# PowerSuply.net
KiCad netlist of a schematic drawn in Altium Designer
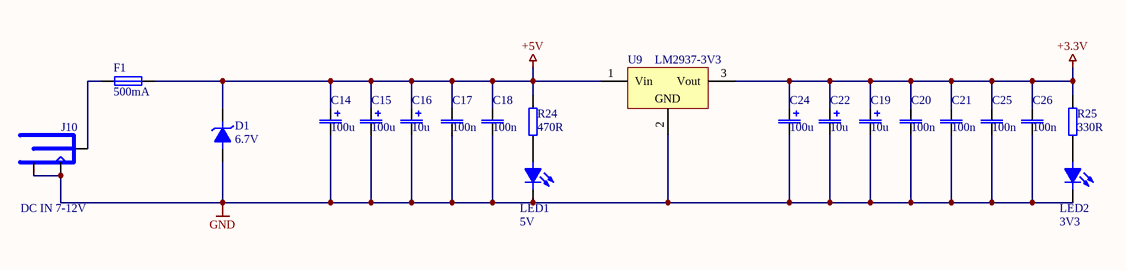
[diagram p0: PowerSuply.SchDoc]

(export (version "E")
  (design (tool "Eeschema 10.0.6"))
  (components
    (comp (ref "C14")
      (value "100u")
      (footprint "D8 ELKO")
      (description "POLARIZED CAPACITOR")
      (libsource (lib "SCH_LIB") (part "CAP_POL"))
    )
    (comp (ref "C15")
      (value "100u")
      (footprint "D8 ELKO")
      (description "POLARIZED CAPACITOR")
      (libsource (lib "SCH_LIB") (part "CAP_POL"))
    )
    (comp (ref "C16")
      (value "10u")
      (footprint "CAP 1210")
      (description "POLARIZED CAPACITOR")
      (libsource (lib "SCH_LIB") (part "CAP_POL"))
    )
    (comp (ref "C17")
      (value "100n")
      (footprint "CAP 0805")
      (description "NON POLARIZED CAPACITOR")
      (libsource (lib "SCH_LIB") (part "CAP"))
    )
    (comp (ref "C18")
      (value "100n")
      (footprint "CAP 0805")
      (description "NON POLARIZED CAPACITOR")
      (libsource (lib "SCH_LIB") (part "CAP"))
    )
    (comp (ref "C19")
      (value "10u")
      (footprint "CAP 1210")
      (description "POLARIZED CAPACITOR")
      (libsource (lib "SCH_LIB") (part "CAP_POL"))
    )
    (comp (ref "C20")
      (value "100n")
      (footprint "CAP 0805")
      (description "NON POLARIZED CAPACITOR")
      (libsource (lib "SCH_LIB") (part "CAP"))
    )
    (comp (ref "C21")
      (value "100n")
      (footprint "CAP 0805")
      (description "NON POLARIZED CAPACITOR")
      (libsource (lib "SCH_LIB") (part "CAP"))
    )
    (comp (ref "C22")
      (value "10u")
      (footprint "CAP 1210")
      (description "POLARIZED CAPACITOR")
      (libsource (lib "SCH_LIB") (part "CAP_POL"))
    )
    (comp (ref "C24")
      (value "100u")
      (footprint "D8 ELKO")
      (description "POLARIZED CAPACITOR")
      (libsource (lib "SCH_LIB") (part "CAP_POL"))
    )
    (comp (ref "C25")
      (value "100n")
      (footprint "CAP 0805")
      (description "NON POLARIZED CAPACITOR")
      (libsource (lib "SCH_LIB") (part "CAP"))
    )
    (comp (ref "C26")
      (value "100n")
      (footprint "CAP 0805")
      (description "NON POLARIZED CAPACITOR")
      (libsource (lib "SCH_LIB") (part "CAP"))
    )
    (comp (ref "D1")
      (value "6.7V")
      (footprint "SMA")
      (description "SUPRESSOR DIODE")
      (libsource (lib "SCH_LIB") (part "SUPRESSOR DIODE"))
    )
    (comp (ref "F1")
      (value "500mA")
      (footprint "FUSE1812")
      (description "FUSE")
      (libsource (lib "SCH_LIB") (part "FUSE"))
    )
    (comp (ref "J10")
      (value "DC IN 7-12V")
      (footprint "DC POWER CONNECTOR")
      (description "DC POWER CONNECTOR 5.5/2.1/9.5mm")
      (libsource (lib "SCH_LIB") (part "DC POWER CONN"))
    )
    (comp (ref "LED1")
      (value "5V")
      (footprint "LED 0805G")
      (description "LED")
      (libsource (lib "SCH_LIB") (part "LED"))
    )
    (comp (ref "LED2")
      (value "3V3")
      (footprint "LED 0805G")
      (description "LED")
      (libsource (lib "SCH_LIB") (part "LED"))
    )
    (comp (ref "R24")
      (value "470R")
      (footprint "RES 0805")
      (description "RESISTOR")
      (libsource (lib "SCH_LIB") (part "RES"))
    )
    (comp (ref "R25")
      (value "330R")
      (footprint "RES 0805")
      (description "RESISTOR")
      (libsource (lib "SCH_LIB") (part "RES"))
    )
    (comp (ref "U9")
      (value "LM2937-3V3")
      (footprint "SOT223")
      (description "SOT223")
      (libsource (lib "SCH_LIB") (part "LM2937"))
    )
  )
  (nets
    (net (code "1") (name "+3.3V") (class "Default")
      (node (ref "C19") (pin "1") (pinfunction "+_1") (pintype "passive"))
      (node (ref "C20") (pin "2") (pinfunction "2_2") (pintype "passive"))
      (node (ref "C21") (pin "2") (pinfunction "2_2") (pintype "passive"))
      (node (ref "C22") (pin "1") (pinfunction "+_1") (pintype "passive"))
      (node (ref "C24") (pin "1") (pinfunction "+_1") (pintype "passive"))
      (node (ref "C25") (pin "2") (pinfunction "2_2") (pintype "passive"))
      (node (ref "C26") (pin "2") (pinfunction "2_2") (pintype "passive"))
      (node (ref "R25") (pin "2") (pinfunction "2_2") (pintype "passive"))
      (node (ref "U9") (pin "3") (pinfunction "Vout_3") (pintype "passive"))
    )
    (net (code "2") (name "+5V") (class "Default")
      (node (ref "C14") (pin "1") (pinfunction "+_1") (pintype "passive"))
      (node (ref "C15") (pin "1") (pinfunction "+_1") (pintype "passive"))
      (node (ref "C16") (pin "1") (pinfunction "+_1") (pintype "passive"))
      (node (ref "C17") (pin "2") (pinfunction "2_2") (pintype "passive"))
      (node (ref "C18") (pin "2") (pinfunction "2_2") (pintype "passive"))
      (node (ref "D1") (pin "2") (pinfunction "K_2") (pintype "passive"))
      (node (ref "F1") (pin "2") (pinfunction "2_2") (pintype "passive"))
      (node (ref "R24") (pin "2") (pinfunction "2_2") (pintype "passive"))
      (node (ref "U9") (pin "1") (pinfunction "Vin_1") (pintype "passive"))
    )
    (net (code "3") (name "GND") (class "Default")
      (node (ref "C14") (pin "2") (pinfunction "-_2") (pintype "passive"))
      (node (ref "C15") (pin "2") (pinfunction "-_2") (pintype "passive"))
      (node (ref "C16") (pin "2") (pinfunction "-_2") (pintype "passive"))
      (node (ref "C17") (pin "1") (pinfunction "1_1") (pintype "passive"))
      (node (ref "C18") (pin "1") (pinfunction "1_1") (pintype "passive"))
      (node (ref "C19") (pin "2") (pinfunction "-_2") (pintype "passive"))
      (node (ref "C20") (pin "1") (pinfunction "1_1") (pintype "passive"))
      (node (ref "C21") (pin "1") (pinfunction "1_1") (pintype "passive"))
      (node (ref "C22") (pin "2") (pinfunction "-_2") (pintype "passive"))
      (node (ref "C24") (pin "2") (pinfunction "-_2") (pintype "passive"))
      (node (ref "C25") (pin "1") (pinfunction "1_1") (pintype "passive"))
      (node (ref "C26") (pin "1") (pinfunction "1_1") (pintype "passive"))
      (node (ref "D1") (pin "1") (pinfunction "A_1") (pintype "passive"))
      (node (ref "J10") (pin "2") (pinfunction "GND_2") (pintype "power_in"))
      (node (ref "J10") (pin "3") (pinfunction "GND_3") (pintype "power_in"))
      (node (ref "LED1") (pin "2") (pinfunction "K_2") (pintype "passive"))
      (node (ref "LED2") (pin "2") (pinfunction "K_2") (pintype "passive"))
      (node (ref "U9") (pin "2") (pinfunction "GND_2") (pintype "passive"))
    )
    (net (code "4") (name "Net-(J10-9V)") (class "Default")
      (node (ref "F1") (pin "1") (pinfunction "2_1") (pintype "passive"))
      (node (ref "J10") (pin "1") (pinfunction "9V_1") (pintype "power_in"))
    )
    (net (code "5") (name "Net-(LED1-A)") (class "Default")
      (node (ref "LED1") (pin "1") (pinfunction "A_1") (pintype "passive"))
      (node (ref "R24") (pin "1") (pinfunction "1_1") (pintype "passive"))
    )
    (net (code "6") (name "Net-(LED2-A)") (class "Default")
      (node (ref "LED2") (pin "1") (pinfunction "A_1") (pintype "passive"))
      (node (ref "R25") (pin "1") (pinfunction "1_1") (pintype "passive"))
    )
  )
)
